# SCH_LED_drill_2025-12-12.net
KiCad netlist of a schematic drawn in EasyEDA
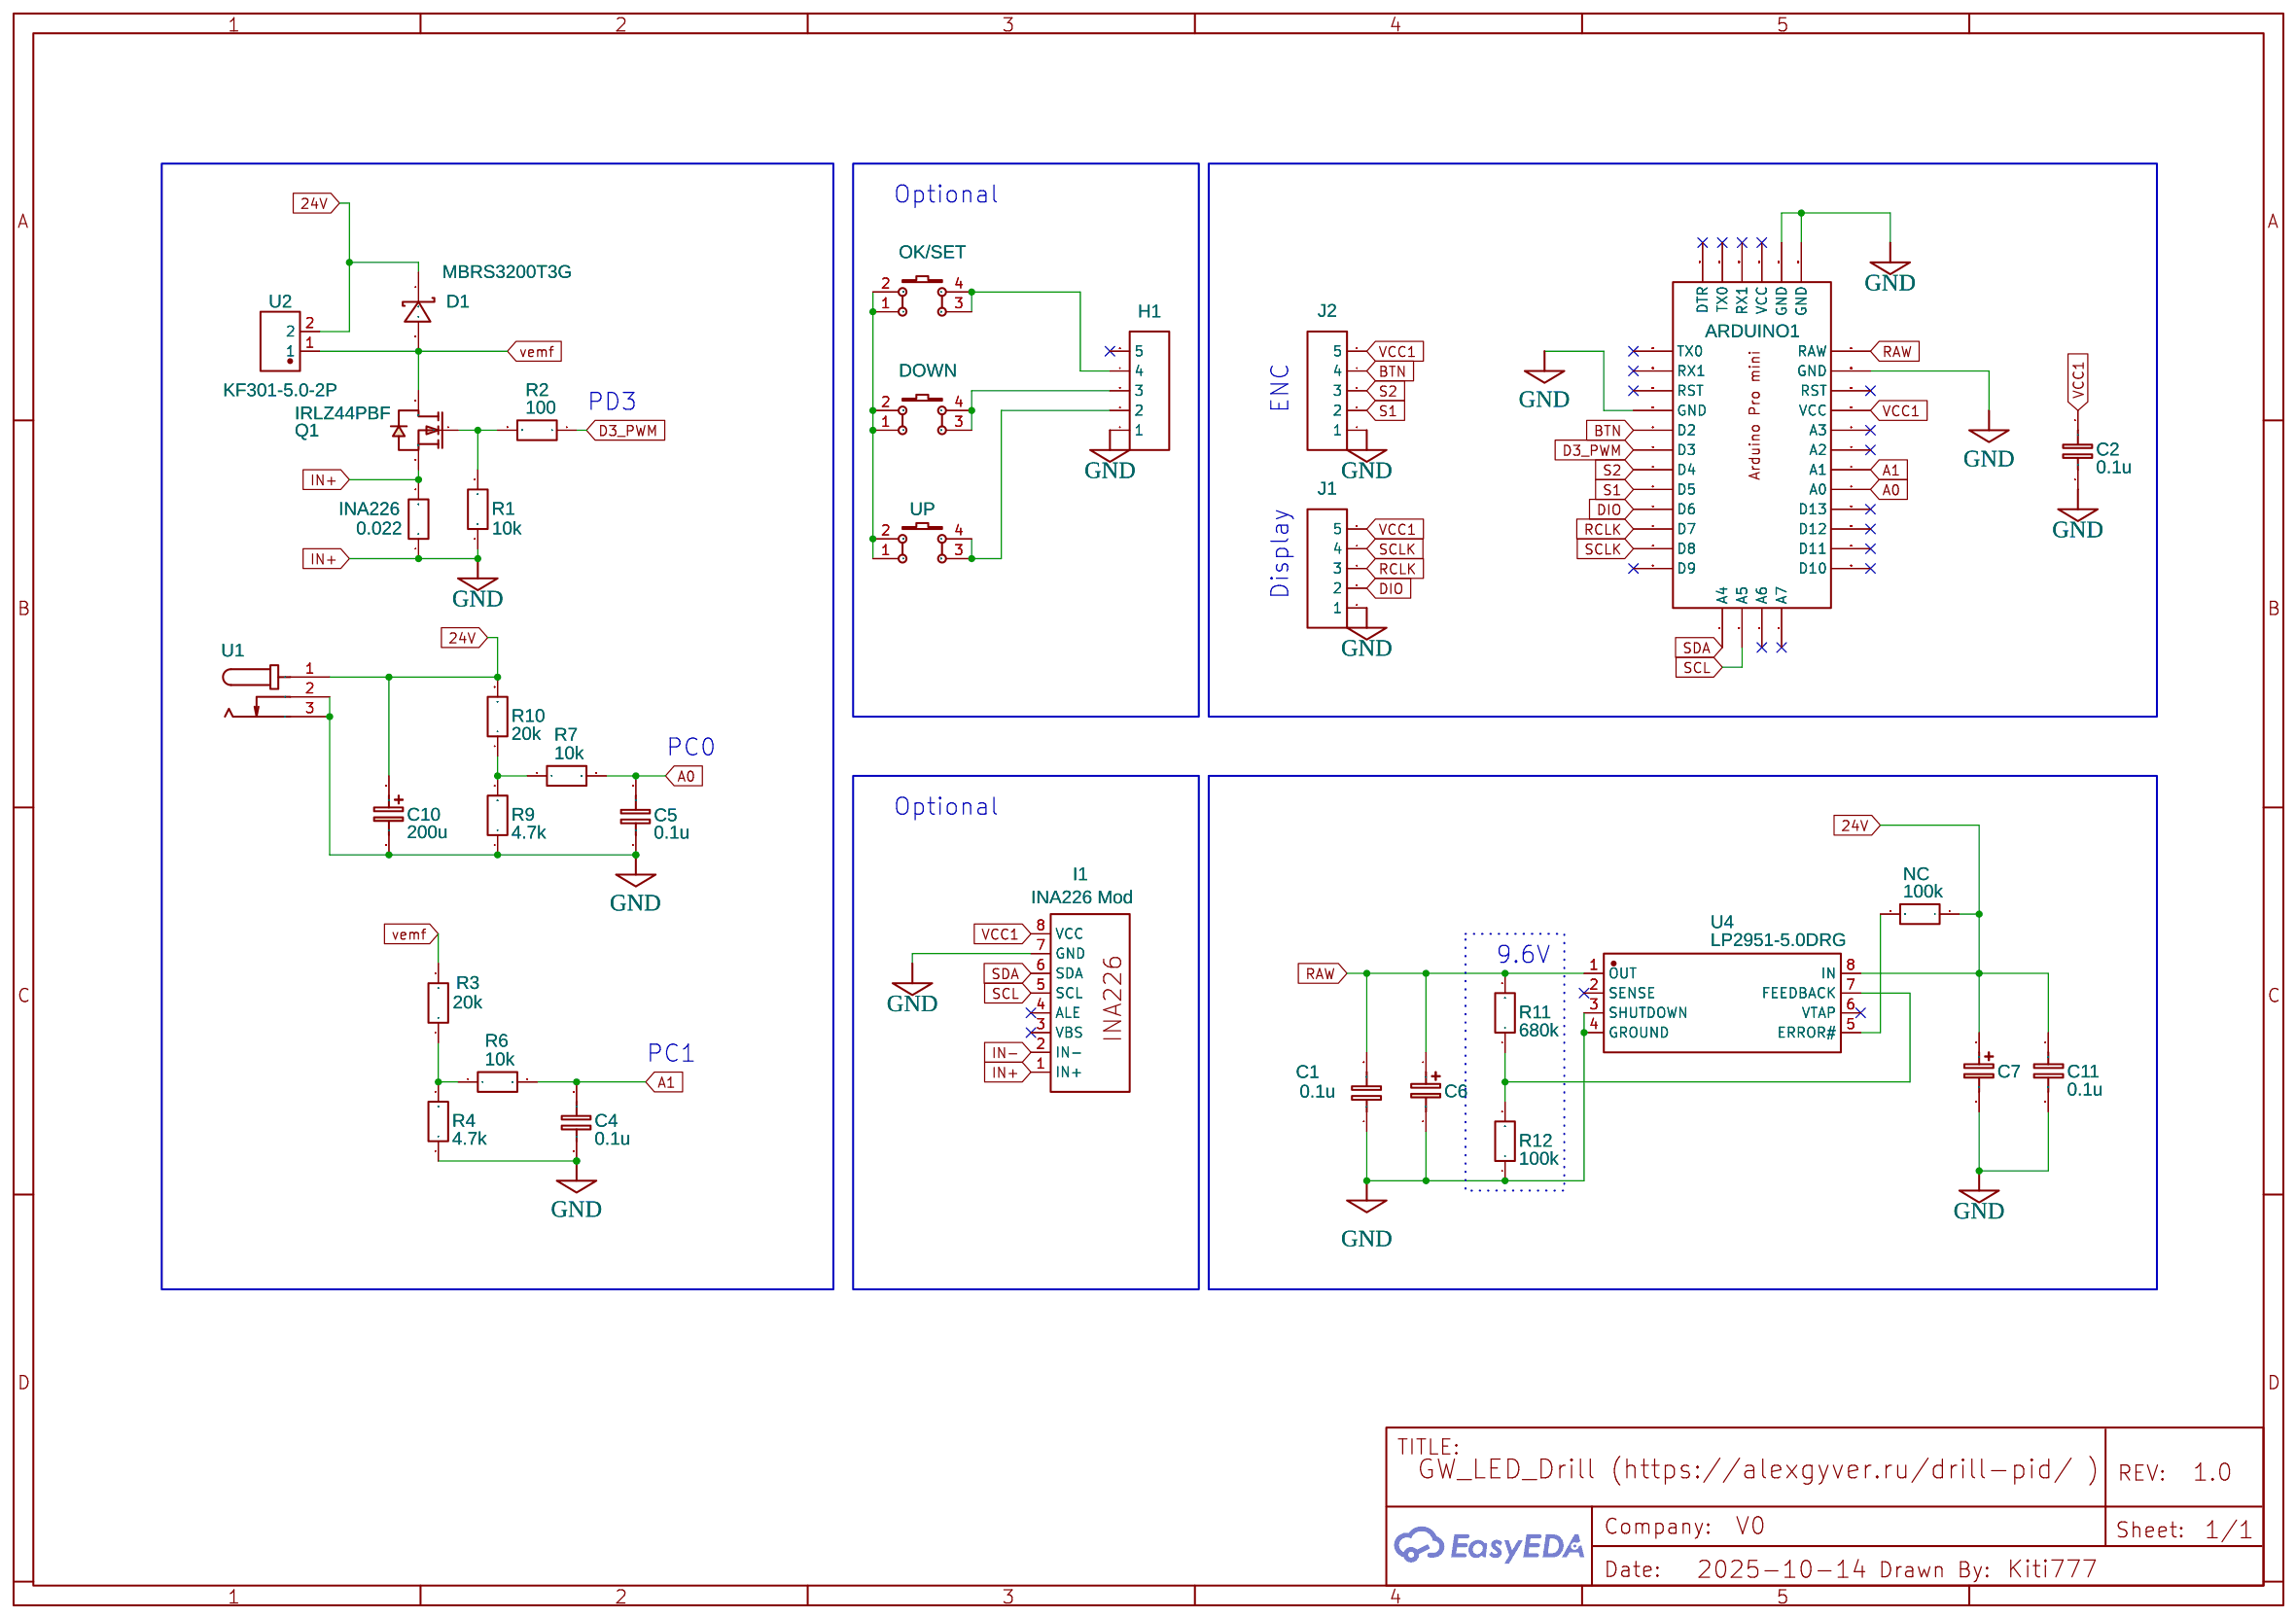
[diagram p0: schematic sheet]

(export (version "E")
  (design (tool "Eeschema 10.0.6"))
  (components
    (comp (ref "ARDUINO1") (value "ARDUINO PRO MINI") (libsource (lib "") (part "ARDUINO PRO MINI")))
    (comp (ref "C1") (value "0.1u") (libsource (lib "") (part "C_1206_EU")))
    (comp (ref "C2") (value "0.1u") (libsource (lib "") (part "C_0805_EU_1")))
    (comp (ref "C4") (value "0.1u") (libsource (lib "") (part "C_0805_EU")))
    (comp (ref "C5") (value "0.1u") (libsource (lib "") (part "C_1206_EU_2")))
    (comp (ref "C6")
      (value "TANTALUM SMT CAPACITOR 330UF C")
      (fields (field (name "Manufacturer Part") "Tantalum SMT Capacitor 330uF C"))
      (libsource (lib "") (part "TANTALUM SMT CAPACITOR 330UF C"))
    )
    (comp (ref "C7")
      (value "TANTALUM SMT CAPACITOR 330UF C")
      (fields (field (name "Manufacturer Part") "Tantalum SMT Capacitor 330uF C"))
      (libsource (lib "") (part "TANTALUM SMT CAPACITOR 330UF C"))
    )
    (comp (ref "C10") (value "200u") (libsource (lib "") (part "CE_SMD_D8.0×H10.5_EU")))
    (comp (ref "C11") (value "0.1u") (libsource (lib "") (part "C_1206_EU_1")))
    (comp (ref "D1")
      (value "MBRS3200T3G")
      (fields (field (name "Manufacturer") "onsemi(安森美)"))
      (libsource (lib "") (part "MBRS3200T3G"))
    )
    (comp (ref "DOWN")
      (value "K4-6×6_TH")
      (fields (field (name "Manufacturer Part") "K2-1102DP-E4SW-04") (field (name "Manufacturer") "韩国韩荣"))
      (libsource (lib "") (part "K4-6×6_TH"))
    )
    (comp (ref "H1") (value "HDR-F-2.54_1x5") (libsource (lib "") (part "HDR-F-2.54_1x5")))
    (comp (ref "I1") (value "INA226 Mod") (libsource (lib "") (part "INA226_1 Modulo")))
    (comp (ref "INA226") (value "0.022") (libsource (lib "") (part "R_2010_EU")))
    (comp (ref "J1") (value "HDR-M-2.54_1x5") (libsource (lib "") (part "HDR-M-2.54_1x5")))
    (comp (ref "J2") (value "HDR-M-2.54_1x5") (libsource (lib "") (part "HDR-M-2.54_1x5")))
    (comp (ref "NC") (value "100k") (libsource (lib "") (part "R_0805_EU_1")))
    (comp (ref "OK/SET")
      (value "K4-6×6_TH")
      (fields (field (name "Manufacturer Part") "K2-1102DP-E4SW-04") (field (name "Manufacturer") "韩国韩荣"))
      (libsource (lib "") (part "K4-6×6_TH_1"))
    )
    (comp (ref "Q1")
      (value "IRLZ44PBF")
      (fields (field (name "Manufacturer Part") "IRLZ44PBF-VB") (field (name "Manufacturer") "VBsemi(微碧半导体)"))
      (libsource (lib "") (part "IRLZ44PBF"))
    )
    (comp (ref "R1") (value "10k") (libsource (lib "") (part "R_1206_EU")))
    (comp (ref "R2") (value "100") (libsource (lib "") (part "R_1206_EU_1")))
    (comp (ref "R3") (value "20k") (libsource (lib "") (part "R_1206_EU")))
    (comp (ref "R4") (value "4.7k") (libsource (lib "") (part "R_1206_EU")))
    (comp (ref "R6") (value "10k") (libsource (lib "") (part "R_1206_EU_2")))
    (comp (ref "R7") (value "10k") (libsource (lib "") (part "R_1206_EU_2")))
    (comp (ref "R9") (value "4.7k") (libsource (lib "") (part "R_1206_EU")))
    (comp (ref "R10") (value "20k") (libsource (lib "") (part "R_1206_EU")))
    (comp (ref "R11") (value "680k") (libsource (lib "") (part "R_0805_EU")))
    (comp (ref "R12") (value "100k") (libsource (lib "") (part "R_0805_EU")))
    (comp (ref "U1")
      (value "ZX-DC-WC26.4")
      (fields (field (name "Manufacturer") "Megastar(兆星)"))
      (libsource (lib "") (part "ZX-DC-WC26.4"))
    )
    (comp (ref "U2")
      (value "KF301-5.0-2P")
      (fields (field (name "Manufacturer") "KEFA(科发)"))
      (libsource (lib "") (part "KF301-5.0-2P"))
    )
    (comp (ref "U4")
      (value "LP2951-5.0DRG")
      (fields (field (name "Manufacturer") "HGC(深圳汉芯)"))
      (libsource (lib "") (part "LP2951-5.0DRG"))
    )
    (comp (ref "UP")
      (value "K4-6×6_TH")
      (fields (field (name "Manufacturer Part") "K2-1102DP-E4SW-04") (field (name "Manufacturer") "韩国韩荣"))
      (libsource (lib "") (part "K4-6×6_TH_2"))
    )
  )
  (nets
    (net (code "1") (name "24V") (class "Default")
      (node (ref "C10") (pin "1") (pinfunction "1_1") (pintype "unspecified"))
      (node (ref "C11") (pin "1") (pinfunction "1_1") (pintype "unspecified"))
      (node (ref "C7") (pin "1") (pinfunction "1_1") (pintype "unspecified"))
      (node (ref "D1") (pin "1") (pinfunction "C_1") (pintype "unspecified"))
      (node (ref "NC") (pin "1") (pinfunction "1_1") (pintype "unspecified"))
      (node (ref "R10") (pin "2") (pinfunction "2_2") (pintype "unspecified"))
      (node (ref "U1") (pin "1") (pinfunction "1_1") (pintype "unspecified"))
      (node (ref "U2") (pin "2") (pinfunction "2_2") (pintype "unspecified"))
      (node (ref "U4") (pin "8") (pinfunction "IN_8") (pintype "unspecified"))
    )
    (net (code "2") (name "A0") (class "Default")
      (node (ref "ARDUINO1") (pin "A0") (pinfunction "A0_A0") (pintype "bidirectional"))
      (node (ref "C5") (pin "2") (pinfunction "2_2") (pintype "unspecified"))
      (node (ref "R7") (pin "2") (pinfunction "2_2") (pintype "unspecified"))
    )
    (net (code "3") (name "A1") (class "Default")
      (node (ref "ARDUINO1") (pin "A1") (pinfunction "A1_A1") (pintype "bidirectional"))
      (node (ref "C4") (pin "2") (pinfunction "2_2") (pintype "unspecified"))
      (node (ref "R6") (pin "2") (pinfunction "2_2") (pintype "unspecified"))
    )
    (net (code "4") (name "BTN") (class "Default")
      (node (ref "ARDUINO1") (pin "D2") (pinfunction "D2_D2") (pintype "bidirectional"))
      (node (ref "J2") (pin "4") (pinfunction "4_4") (pintype "unspecified"))
    )
    (net (code "5") (name "D3_PWM") (class "Default")
      (node (ref "ARDUINO1") (pin "D3") (pinfunction "D3_D3") (pintype "bidirectional"))
      (node (ref "R2") (pin "1") (pinfunction "1_1") (pintype "unspecified"))
    )
    (net (code "6") (name "DIO") (class "Default")
      (node (ref "ARDUINO1") (pin "D6") (pinfunction "D6_D6") (pintype "bidirectional"))
      (node (ref "J1") (pin "2") (pinfunction "2_2") (pintype "unspecified"))
    )
    (net (code "7") (name "IN+") (class "Default")
      (node (ref "ARDUINO1") (pin "GND@0") (pinfunction "GND_GND@0") (pintype "bidirectional"))
      (node (ref "ARDUINO1") (pin "GND@1") (pinfunction "GND_GND@1") (pintype "bidirectional"))
      (node (ref "ARDUINO1") (pin "GND@2") (pinfunction "GND_GND@2") (pintype "bidirectional"))
      (node (ref "ARDUINO1") (pin "GND@3") (pinfunction "GND_GND@3") (pintype "bidirectional"))
      (node (ref "C1") (pin "1") (pinfunction "1_1") (pintype "unspecified"))
      (node (ref "C10") (pin "2") (pinfunction "2_2") (pintype "unspecified"))
      (node (ref "C11") (pin "2") (pinfunction "2_2") (pintype "unspecified"))
      (node (ref "C2") (pin "1") (pinfunction "1_1") (pintype "unspecified"))
      (node (ref "C4") (pin "1") (pinfunction "1_1") (pintype "unspecified"))
      (node (ref "C5") (pin "1") (pinfunction "1_1") (pintype "unspecified"))
      (node (ref "C6") (pin "2") (pinfunction "2_2") (pintype "unspecified"))
      (node (ref "C7") (pin "2") (pinfunction "2_2") (pintype "unspecified"))
      (node (ref "H1") (pin "1") (pinfunction "1_1") (pintype "unspecified"))
      (node (ref "I1") (pin "1") (pinfunction "IN+_1") (pintype "unspecified"))
      (node (ref "I1") (pin "7") (pinfunction "GND_7") (pintype "unspecified"))
      (node (ref "INA226") (pin "1") (pinfunction "1_1") (pintype "unspecified"))
      (node (ref "INA226") (pin "2") (pinfunction "2_2") (pintype "unspecified"))
      (node (ref "J1") (pin "1") (pinfunction "1_1") (pintype "unspecified"))
      (node (ref "J2") (pin "1") (pinfunction "1_1") (pintype "unspecified"))
      (node (ref "Q1") (pin "3") (pinfunction "S_3") (pintype "unspecified"))
      (node (ref "R1") (pin "1") (pinfunction "1_1") (pintype "unspecified"))
      (node (ref "R12") (pin "1") (pinfunction "1_1") (pintype "unspecified"))
      (node (ref "R4") (pin "1") (pinfunction "1_1") (pintype "unspecified"))
      (node (ref "R9") (pin "1") (pinfunction "1_1") (pintype "unspecified"))
      (node (ref "U1") (pin "2") (pinfunction "2_2") (pintype "unspecified"))
      (node (ref "U1") (pin "3") (pinfunction "3_3") (pintype "unspecified"))
      (node (ref "U4") (pin "3") (pinfunction "SHUTDOWN_3") (pintype "unspecified"))
      (node (ref "U4") (pin "4") (pinfunction "GROUND_4") (pintype "unspecified"))
    )
    (net (code "8") (name "IN-") (class "Default")
      (node (ref "I1") (pin "2") (pinfunction "IN-_2") (pintype "unspecified"))
    )
    (net (code "9") (name "Net-(DOWN-Pad1)") (class "Default")
      (node (ref "DOWN") (pin "1") (pinfunction "1_1") (pintype "unspecified"))
      (node (ref "DOWN") (pin "2") (pinfunction "2_2") (pintype "unspecified"))
      (node (ref "OK/SET") (pin "1") (pinfunction "1_1") (pintype "unspecified"))
      (node (ref "OK/SET") (pin "2") (pinfunction "2_2") (pintype "unspecified"))
      (node (ref "UP") (pin "1") (pinfunction "1_1") (pintype "unspecified"))
      (node (ref "UP") (pin "2") (pinfunction "2_2") (pintype "unspecified"))
    )
    (net (code "10") (name "Net-(DOWN-Pad3)") (class "Default")
      (node (ref "DOWN") (pin "3") (pinfunction "3_3") (pintype "unspecified"))
      (node (ref "DOWN") (pin "4") (pinfunction "4_4") (pintype "unspecified"))
      (node (ref "H1") (pin "3") (pinfunction "3_3") (pintype "unspecified"))
    )
    (net (code "11") (name "Net-(H1-Pad2)") (class "Default")
      (node (ref "H1") (pin "2") (pinfunction "2_2") (pintype "unspecified"))
      (node (ref "UP") (pin "3") (pinfunction "3_3") (pintype "unspecified"))
      (node (ref "UP") (pin "4") (pinfunction "4_4") (pintype "unspecified"))
    )
    (net (code "12") (name "Net-(H1-Pad4)") (class "Default")
      (node (ref "H1") (pin "4") (pinfunction "4_4") (pintype "unspecified"))
      (node (ref "OK/SET") (pin "3") (pinfunction "3_3") (pintype "unspecified"))
      (node (ref "OK/SET") (pin "4") (pinfunction "4_4") (pintype "unspecified"))
    )
    (net (code "13") (name "Net-(Q1-G)") (class "Default")
      (node (ref "Q1") (pin "1") (pinfunction "G_1") (pintype "unspecified"))
      (node (ref "R1") (pin "2") (pinfunction "2_2") (pintype "unspecified"))
      (node (ref "R2") (pin "2") (pinfunction "2_2") (pintype "unspecified"))
    )
    (net (code "14") (name "Net-(R3-Pad1)") (class "Default")
      (node (ref "R3") (pin "1") (pinfunction "1_1") (pintype "unspecified"))
      (node (ref "R4") (pin "2") (pinfunction "2_2") (pintype "unspecified"))
      (node (ref "R6") (pin "1") (pinfunction "1_1") (pintype "unspecified"))
    )
    (net (code "15") (name "Net-(R10-Pad1)") (class "Default")
      (node (ref "R10") (pin "1") (pinfunction "1_1") (pintype "unspecified"))
      (node (ref "R7") (pin "1") (pinfunction "1_1") (pintype "unspecified"))
      (node (ref "R9") (pin "2") (pinfunction "2_2") (pintype "unspecified"))
    )
    (net (code "16") (name "Net-(U4-ERROR#)") (class "Default")
      (node (ref "NC") (pin "2") (pinfunction "2_2") (pintype "unspecified"))
      (node (ref "U4") (pin "5") (pinfunction "ERROR#_5") (pintype "unspecified"))
    )
    (net (code "17") (name "Net-(U4-FEEDBACK)") (class "Default")
      (node (ref "R11") (pin "1") (pinfunction "1_1") (pintype "unspecified"))
      (node (ref "R12") (pin "2") (pinfunction "2_2") (pintype "unspecified"))
      (node (ref "U4") (pin "7") (pinfunction "FEEDBACK_7") (pintype "unspecified"))
    )
    (net (code "18") (name "RAW") (class "Default")
      (node (ref "ARDUINO1") (pin "RAW") (pinfunction "RAW_RAW") (pintype "bidirectional"))
      (node (ref "C1") (pin "2") (pinfunction "2_2") (pintype "unspecified"))
      (node (ref "C6") (pin "1") (pinfunction "1_1") (pintype "unspecified"))
      (node (ref "R11") (pin "2") (pinfunction "2_2") (pintype "unspecified"))
      (node (ref "U4") (pin "1") (pinfunction "OUT_1") (pintype "unspecified"))
    )
    (net (code "19") (name "RCLK") (class "Default")
      (node (ref "ARDUINO1") (pin "D7") (pinfunction "D7_D7") (pintype "bidirectional"))
      (node (ref "J1") (pin "3") (pinfunction "3_3") (pintype "unspecified"))
    )
    (net (code "20") (name "S1") (class "Default")
      (node (ref "ARDUINO1") (pin "D5") (pinfunction "D5_D5") (pintype "bidirectional"))
      (node (ref "J2") (pin "2") (pinfunction "2_2") (pintype "unspecified"))
    )
    (net (code "21") (name "S2") (class "Default")
      (node (ref "ARDUINO1") (pin "D4") (pinfunction "D4_D4") (pintype "bidirectional"))
      (node (ref "J2") (pin "3") (pinfunction "3_3") (pintype "unspecified"))
    )
    (net (code "22") (name "SCL") (class "Default")
      (node (ref "ARDUINO1") (pin "A5") (pinfunction "A5_A5") (pintype "bidirectional"))
      (node (ref "I1") (pin "5") (pinfunction "SCL_5") (pintype "unspecified"))
    )
    (net (code "23") (name "SCLK") (class "Default")
      (node (ref "ARDUINO1") (pin "D8") (pinfunction "D8_D8") (pintype "bidirectional"))
      (node (ref "J1") (pin "4") (pinfunction "4_4") (pintype "unspecified"))
    )
    (net (code "24") (name "SDA") (class "Default")
      (node (ref "ARDUINO1") (pin "A4") (pinfunction "A4_A4") (pintype "bidirectional"))
      (node (ref "I1") (pin "6") (pinfunction "SDA_6") (pintype "unspecified"))
    )
    (net (code "25") (name "VCC1") (class "Default")
      (node (ref "ARDUINO1") (pin "VCC@1") (pinfunction "VCC_VCC@1") (pintype "bidirectional"))
      (node (ref "C2") (pin "2") (pinfunction "2_2") (pintype "unspecified"))
      (node (ref "I1") (pin "8") (pinfunction "VCC_8") (pintype "unspecified"))
      (node (ref "J1") (pin "5") (pinfunction "5_5") (pintype "unspecified"))
      (node (ref "J2") (pin "5") (pinfunction "5_5") (pintype "unspecified"))
    )
    (net (code "26") (name "unconnected-(ARDUINO1-PadA2)") (class "Default")
      (node (ref "ARDUINO1") (pin "A2") (pinfunction "A2_A2") (pintype "bidirectional+no_connect"))
    )
    (net (code "27") (name "unconnected-(ARDUINO1-PadA3)") (class "Default")
      (node (ref "ARDUINO1") (pin "A3") (pinfunction "A3_A3") (pintype "bidirectional+no_connect"))
    )
    (net (code "28") (name "unconnected-(ARDUINO1-PadA6)") (class "Default")
      (node (ref "ARDUINO1") (pin "A6") (pinfunction "A6_A6") (pintype "bidirectional+no_connect"))
    )
    (net (code "29") (name "unconnected-(ARDUINO1-PadA7)") (class "Default")
      (node (ref "ARDUINO1") (pin "A7") (pinfunction "A7_A7") (pintype "bidirectional+no_connect"))
    )
    (net (code "30") (name "unconnected-(ARDUINO1-PadD9)") (class "Default")
      (node (ref "ARDUINO1") (pin "D9") (pinfunction "D9_D9") (pintype "bidirectional+no_connect"))
    )
    (net (code "31") (name "unconnected-(ARDUINO1-PadD10)") (class "Default")
      (node (ref "ARDUINO1") (pin "D10") (pinfunction "D10_D10") (pintype "bidirectional+no_connect"))
    )
    (net (code "32") (name "unconnected-(ARDUINO1-PadD11)") (class "Default")
      (node (ref "ARDUINO1") (pin "D11") (pinfunction "D11_D11") (pintype "bidirectional+no_connect"))
    )
    (net (code "33") (name "unconnected-(ARDUINO1-PadD12)") (class "Default")
      (node (ref "ARDUINO1") (pin "D12") (pinfunction "D12_D12") (pintype "bidirectional+no_connect"))
    )
    (net (code "34") (name "unconnected-(ARDUINO1-PadD13)") (class "Default")
      (node (ref "ARDUINO1") (pin "D13") (pinfunction "D13_D13") (pintype "bidirectional+no_connect"))
    )
    (net (code "35") (name "unconnected-(ARDUINO1-PadDTR)") (class "Default")
      (node (ref "ARDUINO1") (pin "DTR") (pinfunction "DTR_DTR") (pintype "bidirectional+no_connect"))
    )
    (net (code "36") (name "unconnected-(ARDUINO1-RST-PadRST@0)") (class "Default")
      (node (ref "ARDUINO1") (pin "RST@0") (pinfunction "RST_RST@0") (pintype "bidirectional+no_connect"))
    )
    (net (code "37") (name "unconnected-(ARDUINO1-RST-PadRST@1)") (class "Default")
      (node (ref "ARDUINO1") (pin "RST@1") (pinfunction "RST_RST@1") (pintype "bidirectional+no_connect"))
    )
    (net (code "38") (name "unconnected-(ARDUINO1-RX1-PadRX1@0)") (class "Default")
      (node (ref "ARDUINO1") (pin "RX1@0") (pinfunction "RX1_RX1@0") (pintype "bidirectional+no_connect"))
    )
    (net (code "39") (name "unconnected-(ARDUINO1-RX1-PadRX1@1)") (class "Default")
      (node (ref "ARDUINO1") (pin "RX1@1") (pinfunction "RX1_RX1@1") (pintype "bidirectional+no_connect"))
    )
    (net (code "40") (name "unconnected-(ARDUINO1-TX0-PadTX0@0)") (class "Default")
      (node (ref "ARDUINO1") (pin "TX0@0") (pinfunction "TX0_TX0@0") (pintype "bidirectional+no_connect"))
    )
    (net (code "41") (name "unconnected-(ARDUINO1-TX0-PadTX0@1)") (class "Default")
      (node (ref "ARDUINO1") (pin "TX0@1") (pinfunction "TX0_TX0@1") (pintype "bidirectional+no_connect"))
    )
    (net (code "42") (name "unconnected-(ARDUINO1-VCC-PadVCC@0)") (class "Default")
      (node (ref "ARDUINO1") (pin "VCC@0") (pinfunction "VCC_VCC@0") (pintype "bidirectional+no_connect"))
    )
    (net (code "43") (name "unconnected-(H1-Pad5)") (class "Default")
      (node (ref "H1") (pin "5") (pinfunction "5_5") (pintype "unspecified+no_connect"))
    )
    (net (code "44") (name "unconnected-(I1-ALE-Pad4)") (class "Default")
      (node (ref "I1") (pin "4") (pinfunction "ALE_4") (pintype "unspecified+no_connect"))
    )
    (net (code "45") (name "unconnected-(I1-VBS-Pad3)") (class "Default")
      (node (ref "I1") (pin "3") (pinfunction "VBS_3") (pintype "unspecified+no_connect"))
    )
    (net (code "46") (name "unconnected-(U4-SENSE-Pad2)") (class "Default")
      (node (ref "U4") (pin "2") (pinfunction "SENSE_2") (pintype "unspecified+no_connect"))
    )
    (net (code "47") (name "unconnected-(U4-VTAP-Pad6)") (class "Default")
      (node (ref "U4") (pin "6") (pinfunction "VTAP_6") (pintype "unspecified+no_connect"))
    )
    (net (code "48") (name "vemf") (class "Default")
      (node (ref "D1") (pin "2") (pinfunction "A_2") (pintype "unspecified"))
      (node (ref "Q1") (pin "2") (pinfunction "D_2") (pintype "unspecified"))
      (node (ref "R3") (pin "2") (pinfunction "2_2") (pintype "unspecified"))
      (node (ref "U2") (pin "1") (pinfunction "1_1") (pintype "unspecified"))
    )
  )
)
